# oneboard.net
KiCad netlist of a schematic drawn in EAGLE
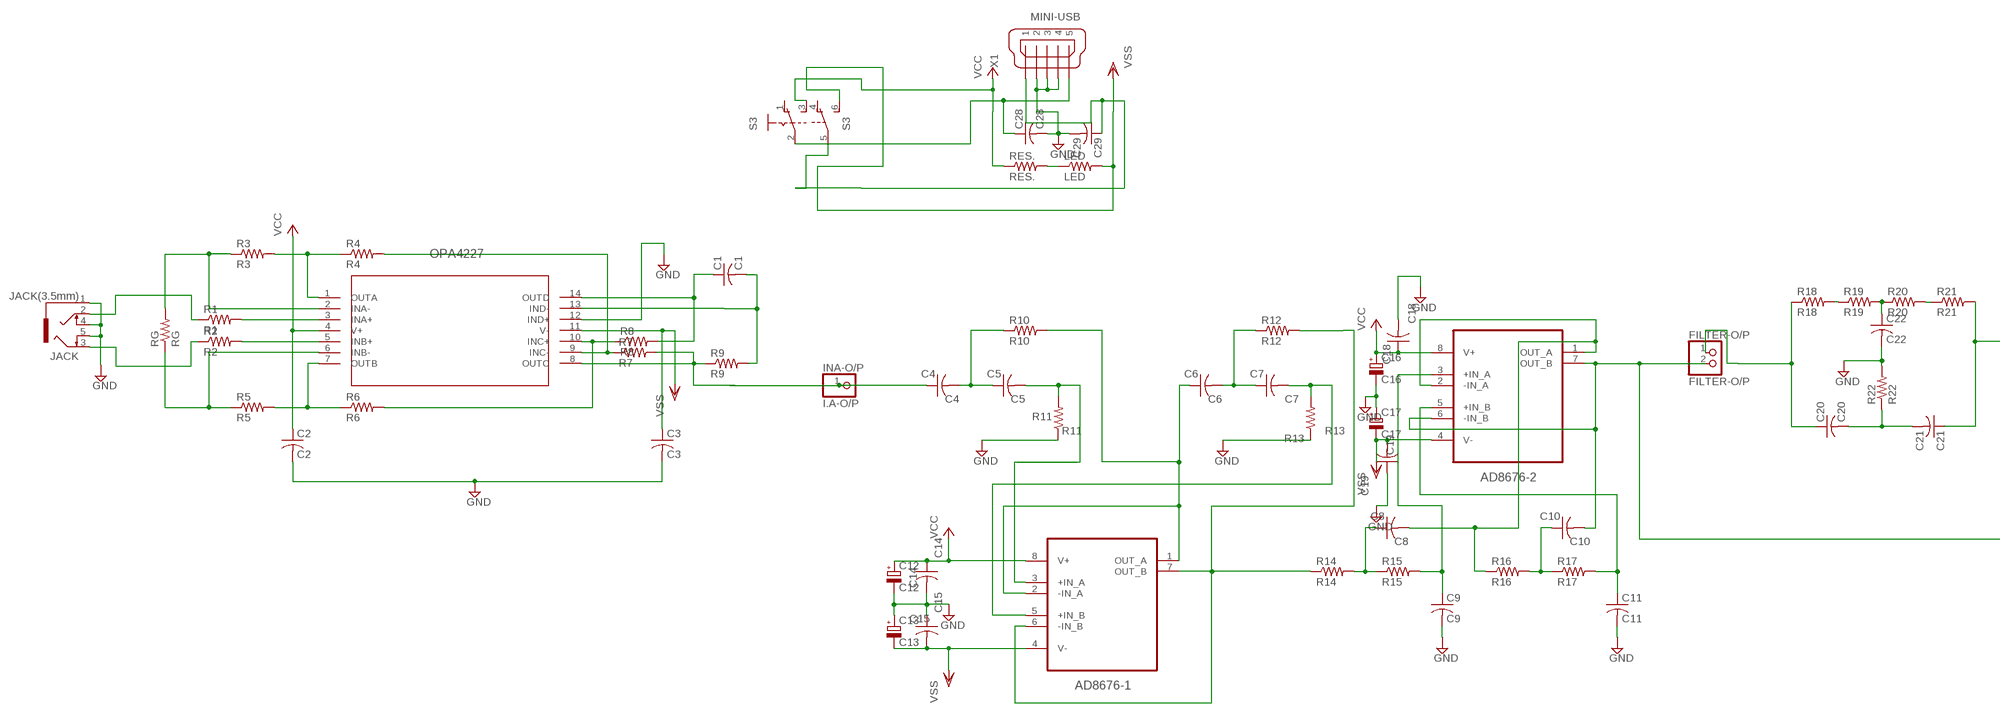
[diagram p0: schematic, sheet 1, part 1 of 2]
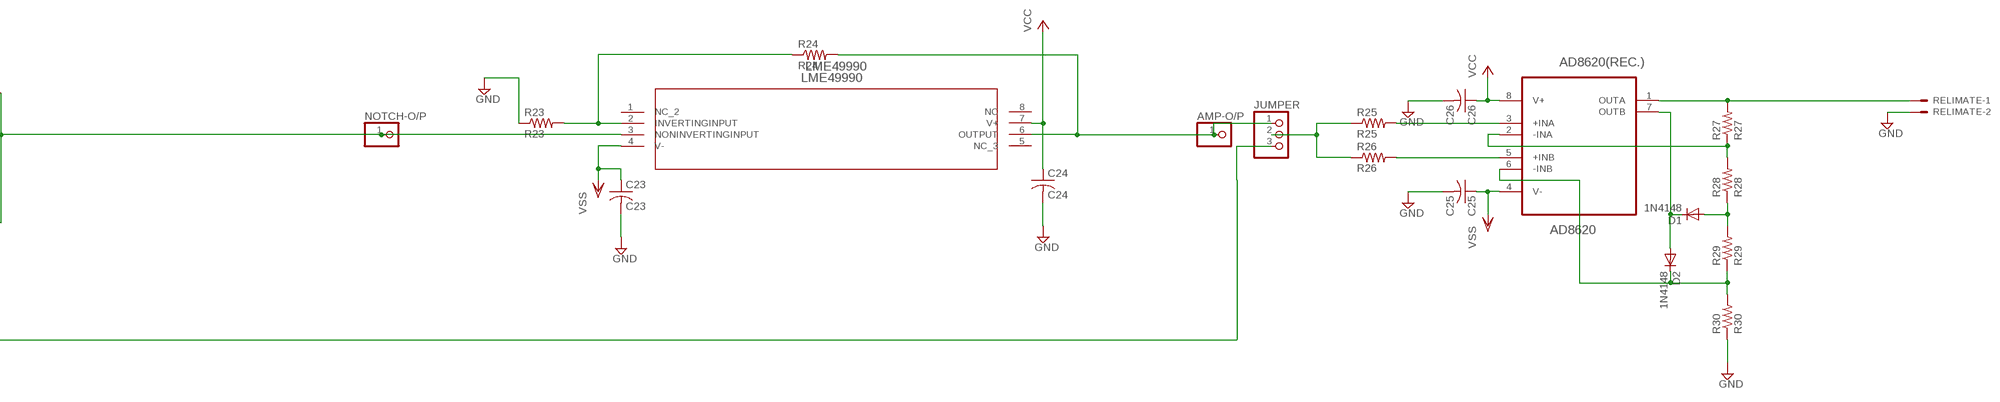
[diagram p1: schematic, sheet 1, part 2 of 2]

(export (version "E")
  (design (tool "Eeschema 10.0.6"))
  (components
    (comp (ref "AD8620(REC.)")
      (value "AD8620")
      (footprint "eagle-import:SOIC127P600X175-8N")
      (fields (field (name "MPN") "AD8620ARZ"))
      (libsource (lib "eagle-import") (part "AD8620ARZ"))
    )
    (comp (ref "AD8676-1")
      (value "AD8676-1")
      (footprint "eagle-import:SOIC127P600X175-8N")
      (fields (field (name "MPN") "AD8676ARZ"))
      (libsource (lib "eagle-import") (part "AD8676ARZ"))
    )
    (comp (ref "AD8676-2")
      (value "AD8676-2")
      (footprint "eagle-import:SOIC127P600X175-8N")
      (fields (field (name "MPN") "AD8676ARZ"))
      (libsource (lib "eagle-import") (part "AD8676ARZ"))
    )
    (comp (ref "AMP-O/P")
      (value "PINHD-1X1")
      (footprint "eagle-import:1X01")
      (libsource (lib "eagle-import") (part "PINHD-1X1"))
    )
    (comp (ref "C1")
      (value "C1")
      (footprint "eagle-import:C0603")
      (libsource (lib "eagle-import") (part "C-USC0603"))
    )
    (comp (ref "C2")
      (value "C2")
      (footprint "eagle-import:C0603")
      (libsource (lib "eagle-import") (part "C-USC0603"))
    )
    (comp (ref "C3")
      (value "C3")
      (footprint "eagle-import:C0603")
      (libsource (lib "eagle-import") (part "C-USC0603"))
    )
    (comp (ref "C4")
      (value "C4")
      (footprint "eagle-import:C0603")
      (libsource (lib "eagle-import") (part "C-USC0603"))
    )
    (comp (ref "C5")
      (value "C5")
      (footprint "eagle-import:C0603")
      (libsource (lib "eagle-import") (part "C-USC0603"))
    )
    (comp (ref "C6")
      (value "C6")
      (footprint "eagle-import:C0603")
      (libsource (lib "eagle-import") (part "C-USC0603"))
    )
    (comp (ref "C7")
      (value "C7")
      (footprint "eagle-import:C0603")
      (libsource (lib "eagle-import") (part "C-USC0603"))
    )
    (comp (ref "C8")
      (value "C8")
      (footprint "eagle-import:C0603")
      (libsource (lib "eagle-import") (part "C-USC0603"))
    )
    (comp (ref "C9")
      (value "C9")
      (footprint "eagle-import:C0603")
      (libsource (lib "eagle-import") (part "C-USC0603"))
    )
    (comp (ref "C10")
      (value "C10")
      (footprint "eagle-import:C0603")
      (libsource (lib "eagle-import") (part "C-USC0603"))
    )
    (comp (ref "C11")
      (value "C11")
      (footprint "eagle-import:C0603")
      (libsource (lib "eagle-import") (part "C-USC0603"))
    )
    (comp (ref "C12")
      (value "C12")
      (footprint "eagle-import:E2-5")
      (libsource (lib "eagle-import") (part "CPOL-EUE2-5"))
    )
    (comp (ref "C13")
      (value "C13")
      (footprint "eagle-import:E2-5")
      (libsource (lib "eagle-import") (part "CPOL-EUE2-5"))
    )
    (comp (ref "C14")
      (value "C14")
      (footprint "eagle-import:C0603")
      (libsource (lib "eagle-import") (part "C-USC0603"))
    )
    (comp (ref "C15")
      (value "C15")
      (footprint "eagle-import:C0603")
      (libsource (lib "eagle-import") (part "C-USC0603"))
    )
    (comp (ref "C16")
      (value "C16")
      (footprint "eagle-import:E2-5")
      (libsource (lib "eagle-import") (part "CPOL-EUE2-5"))
    )
    (comp (ref "C17")
      (value "C17")
      (footprint "eagle-import:E2-5")
      (libsource (lib "eagle-import") (part "CPOL-EUE2-5"))
    )
    (comp (ref "C18")
      (value "C18")
      (footprint "eagle-import:C0603")
      (libsource (lib "eagle-import") (part "C-USC0603"))
    )
    (comp (ref "C19")
      (value "C19")
      (footprint "eagle-import:C0603")
      (libsource (lib "eagle-import") (part "C-USC0603"))
    )
    (comp (ref "C20")
      (value "C20")
      (footprint "eagle-import:C0603")
      (libsource (lib "eagle-import") (part "C-USC0603"))
    )
    (comp (ref "C21")
      (value "C21")
      (footprint "eagle-import:C0603")
      (libsource (lib "eagle-import") (part "C-USC0603"))
    )
    (comp (ref "C22")
      (value "C22")
      (footprint "eagle-import:C0603")
      (libsource (lib "eagle-import") (part "C-USC0603"))
    )
    (comp (ref "C23")
      (value "C23")
      (footprint "eagle-import:C0603")
      (libsource (lib "eagle-import") (part "C-USC0603"))
    )
    (comp (ref "C24")
      (value "C24")
      (footprint "eagle-import:C0603")
      (libsource (lib "eagle-import") (part "C-USC0603"))
    )
    (comp (ref "C25")
      (value "C25")
      (footprint "eagle-import:C0603")
      (libsource (lib "eagle-import") (part "C-USC0603"))
    )
    (comp (ref "C26")
      (value "C26")
      (footprint "eagle-import:C0603")
      (libsource (lib "eagle-import") (part "C-USC0603"))
    )
    (comp (ref "C28")
      (value "C28")
      (footprint "eagle-import:C0603")
      (libsource (lib "eagle-import") (part "C-USC0603"))
    )
    (comp (ref "C29")
      (value "C29")
      (footprint "eagle-import:C0603")
      (libsource (lib "eagle-import") (part "C-USC0603"))
    )
    (comp (ref "D1")
      (value "1N4148")
      (footprint "eagle-import:DO35-10")
      (libsource (lib "eagle-import") (part "1N4148DO35-10"))
    )
    (comp (ref "D2")
      (value "1N4148")
      (footprint "eagle-import:DO35-10")
      (libsource (lib "eagle-import") (part "1N4148DO35-10"))
    )
    (comp (ref "FILTER-O/P")
      (value "FILTER-O/P")
      (footprint "eagle-import:1X02")
      (libsource (lib "eagle-import") (part "PINHD-1X2"))
    )
    (comp (ref "INA-O/P")
      (value "I.A-O/P")
      (footprint "eagle-import:1X01")
      (libsource (lib "eagle-import") (part "PINHD-1X1"))
    )
    (comp (ref "JACK")
      (value "JACK(3.5mm)")
      (footprint "eagle-import:1503_09")
      (libsource (lib "eagle-import") (part "1503_09"))
    )
    (comp (ref "JUMPER")
      (value "PINHD-1X3")
      (footprint "eagle-import:1X03")
      (libsource (lib "eagle-import") (part "PINHD-1X3"))
    )
    (comp (ref "LED")
      (value "LED")
      (footprint "eagle-import:R0805")
      (libsource (lib "eagle-import") (part "R-US_R0805"))
    )
    (comp (ref "LME49990")
      (value "LME49990")
      (footprint "eagle-import:M08A")
      (fields
        (field (name "MANUFACTURER") "Texas Instruments")
        (field (name "MANUFACTURER_PART_NUMBER") "lme49990_d_8")
      )
      (libsource (lib "eagle-import") (part "LME49990_D_8"))
    )
    (comp (ref "NOTCH-O/P")
      (value "PINHD-1X1")
      (footprint "eagle-import:1X01")
      (libsource (lib "eagle-import") (part "PINHD-1X1"))
    )
    (comp (ref "OPA4227")
      (value "OPA4277_D_14")
      (footprint "eagle-import:D14")
      (fields
        (field (name "GENERIC_PART_NUMBER") "OPA4277")
        (field (name "MANUFACTURER") "Texas Instruments")
        (field (name "MANUFACTURER_PART_NUMBER") "opa4277_d_14")
      )
      (libsource (lib "eagle-import") (part "OPA4277_D_14"))
    )
    (comp (ref "R1")
      (value "R1")
      (footprint "eagle-import:R0603")
      (libsource (lib "eagle-import") (part "resistor_R-US_R0603"))
    )
    (comp (ref "R2")
      (value "R2")
      (footprint "eagle-import:R0603")
      (libsource (lib "eagle-import") (part "resistor_R-US_R0603"))
    )
    (comp (ref "R3")
      (value "R3")
      (footprint "eagle-import:R0603")
      (libsource (lib "eagle-import") (part "resistor_R-US_R0603"))
    )
    (comp (ref "R4")
      (value "R4")
      (footprint "eagle-import:R0603")
      (libsource (lib "eagle-import") (part "resistor_R-US_R0603"))
    )
    (comp (ref "R5")
      (value "R5")
      (footprint "eagle-import:R0603")
      (libsource (lib "eagle-import") (part "resistor_R-US_R0603"))
    )
    (comp (ref "R6")
      (value "R6")
      (footprint "eagle-import:R0603")
      (libsource (lib "eagle-import") (part "resistor_R-US_R0603"))
    )
    (comp (ref "R7")
      (value "R7")
      (footprint "eagle-import:R0603")
      (libsource (lib "eagle-import") (part "resistor_R-US_R0603"))
    )
    (comp (ref "R8")
      (value "R8")
      (footprint "eagle-import:R0603")
      (libsource (lib "eagle-import") (part "resistor_R-US_R0603"))
    )
    (comp (ref "R9")
      (value "R9")
      (footprint "eagle-import:R0603")
      (libsource (lib "eagle-import") (part "resistor_R-US_R0603"))
    )
    (comp (ref "R10")
      (value "R10")
      (footprint "eagle-import:R0603")
      (libsource (lib "eagle-import") (part "R-US_R0603"))
    )
    (comp (ref "R11")
      (value "R11")
      (footprint "eagle-import:R0603")
      (libsource (lib "eagle-import") (part "R-US_R0603"))
    )
    (comp (ref "R12")
      (value "R12")
      (footprint "eagle-import:R0603")
      (libsource (lib "eagle-import") (part "R-US_R0603"))
    )
    (comp (ref "R13")
      (value "R13")
      (footprint "eagle-import:R0603")
      (libsource (lib "eagle-import") (part "R-US_R0603"))
    )
    (comp (ref "R14")
      (value "R14")
      (footprint "eagle-import:R0603")
      (libsource (lib "eagle-import") (part "R-US_R0603"))
    )
    (comp (ref "R15")
      (value "R15")
      (footprint "eagle-import:R0603")
      (libsource (lib "eagle-import") (part "R-US_R0603"))
    )
    (comp (ref "R16")
      (value "R16")
      (footprint "eagle-import:R0603")
      (libsource (lib "eagle-import") (part "R-US_R0603"))
    )
    (comp (ref "R17")
      (value "R17")
      (footprint "eagle-import:R0603")
      (libsource (lib "eagle-import") (part "R-US_R0603"))
    )
    (comp (ref "R18")
      (value "R18")
      (footprint "eagle-import:R0603")
      (libsource (lib "eagle-import") (part "R-US_R0603"))
    )
    (comp (ref "R19")
      (value "R19")
      (footprint "eagle-import:R0603")
      (libsource (lib "eagle-import") (part "R-US_R0603"))
    )
    (comp (ref "R20")
      (value "R20")
      (footprint "eagle-import:R0603")
      (libsource (lib "eagle-import") (part "R-US_R0603"))
    )
    (comp (ref "R21")
      (value "R21")
      (footprint "eagle-import:R0603")
      (libsource (lib "eagle-import") (part "R-US_R0603"))
    )
    (comp (ref "R22")
      (value "R22")
      (footprint "eagle-import:R0603")
      (libsource (lib "eagle-import") (part "R-US_R0603"))
    )
    (comp (ref "R23")
      (value "R23")
      (footprint "eagle-import:R0603")
      (libsource (lib "eagle-import") (part "R-US_R0603"))
    )
    (comp (ref "R24")
      (value "R24")
      (footprint "eagle-import:R0603")
      (libsource (lib "eagle-import") (part "R-US_R0603"))
    )
    (comp (ref "R25")
      (value "R25")
      (footprint "eagle-import:R0603")
      (libsource (lib "eagle-import") (part "R-US_R0603"))
    )
    (comp (ref "R26")
      (value "R26")
      (footprint "eagle-import:R0603")
      (libsource (lib "eagle-import") (part "R-US_R0603"))
    )
    (comp (ref "R27")
      (value "R27")
      (footprint "eagle-import:R0603")
      (libsource (lib "eagle-import") (part "R-US_R0603"))
    )
    (comp (ref "R28")
      (value "R28")
      (footprint "eagle-import:R0603")
      (libsource (lib "eagle-import") (part "R-US_R0603"))
    )
    (comp (ref "R29")
      (value "R29")
      (footprint "eagle-import:R0603")
      (libsource (lib "eagle-import") (part "R-US_R0603"))
    )
    (comp (ref "R30")
      (value "R30")
      (footprint "eagle-import:R0603")
      (libsource (lib "eagle-import") (part "R-US_R0603"))
    )
    (comp (ref "RELIMATE")
      (value "22-23-2021")
      (footprint "eagle-import:22-23-2021")
      (fields (field (name "MF") "MOLEX"))
      (libsource (lib "eagle-import") (part "22-23-2021"))
    )
    (comp (ref "RES.")
      (value "RES.")
      (footprint "eagle-import:R0603")
      (libsource (lib "eagle-import") (part "R-US_R0603"))
    )
    (comp (ref "RG")
      (value "RG")
      (footprint "eagle-import:R0603")
      (libsource (lib "eagle-import") (part "resistor_R-US_R0603"))
    )
    (comp (ref "S3")
      (value "A68-A31")
      (footprint "eagle-import:A68-A31")
      (libsource (lib "eagle-import") (part "A68-A31"))
    )
    (comp (ref "X1")
      (value "MINI-USB")
      (footprint "eagle-import:UX60-MB-5S8")
      (libsource (lib "eagle-import") (part "MINI-USB-UX60-MB-5S8"))
    )
  )
  (nets
    (net (code "1") (name "GND") (class "Default")
      (node (ref "C11") (pin "2") (pinfunction "2_2") (pintype "passive"))
      (node (ref "C12") (pin "-") (pinfunction "-_-") (pintype "passive"))
      (node (ref "C13") (pin "+") (pinfunction "+_+") (pintype "passive"))
      (node (ref "C14") (pin "2") (pinfunction "2_2") (pintype "passive"))
      (node (ref "C15") (pin "1") (pinfunction "1_1") (pintype "passive"))
      (node (ref "C16") (pin "-") (pinfunction "-_-") (pintype "passive"))
      (node (ref "C17") (pin "+") (pinfunction "+_+") (pintype "passive"))
      (node (ref "C18") (pin "2") (pinfunction "2_2") (pintype "passive"))
      (node (ref "C19") (pin "1") (pinfunction "1_1") (pintype "passive"))
      (node (ref "C2") (pin "2") (pinfunction "2_2") (pintype "passive"))
      (node (ref "C22") (pin "2") (pinfunction "2_2") (pintype "passive"))
      (node (ref "C23") (pin "2") (pinfunction "2_2") (pintype "passive"))
      (node (ref "C24") (pin "2") (pinfunction "2_2") (pintype "passive"))
      (node (ref "C25") (pin "2") (pinfunction "2_2") (pintype "passive"))
      (node (ref "C26") (pin "2") (pinfunction "2_2") (pintype "passive"))
      (node (ref "C28") (pin "2") (pinfunction "2_2") (pintype "passive"))
      (node (ref "C29") (pin "2") (pinfunction "2_2") (pintype "passive"))
      (node (ref "C3") (pin "2") (pinfunction "2_2") (pintype "passive"))
      (node (ref "C9") (pin "2") (pinfunction "2_2") (pintype "passive"))
      (node (ref "JACK") (pin "1") (pinfunction "1_1") (pintype "passive"))
      (node (ref "JACK") (pin "4") (pinfunction "4_4") (pintype "passive"))
      (node (ref "JACK") (pin "5") (pinfunction "5_5") (pintype "passive"))
      (node (ref "OPA4227") (pin "12") (pinfunction "IND+_12") (pintype "input"))
      (node (ref "R11") (pin "1") (pinfunction "1_1") (pintype "passive"))
      (node (ref "R13") (pin "1") (pinfunction "1_1") (pintype "passive"))
      (node (ref "R22") (pin "2") (pinfunction "2_2") (pintype "passive"))
      (node (ref "R23") (pin "1") (pinfunction "1_1") (pintype "passive"))
      (node (ref "R30") (pin "1") (pinfunction "1_1") (pintype "passive"))
      (node (ref "RELIMATE") (pin "2") (pinfunction "S_2") (pintype "passive"))
      (node (ref "X1") (pin "2") (pinfunction "2_2") (pintype "input"))
      (node (ref "X1") (pin "3") (pinfunction "3_3") (pintype "input"))
      (node (ref "X1") (pin "4") (pinfunction "4_4") (pintype "input"))
    )
    (net (code "2") (name "Net-(AD8620(REC.)-+INA)") (class "Default")
      (node (ref "AD8620(REC.)") (pin "3") (pinfunction "+INA_3") (pintype "input"))
      (node (ref "R25") (pin "2") (pinfunction "2_2") (pintype "passive"))
    )
    (net (code "3") (name "Net-(AD8620(REC.)-+INB)") (class "Default")
      (node (ref "AD8620(REC.)") (pin "5") (pinfunction "+INB_5") (pintype "input"))
      (node (ref "R26") (pin "2") (pinfunction "2_2") (pintype "passive"))
    )
    (net (code "4") (name "Net-(AD8620(REC.)--INA)") (class "Default")
      (node (ref "AD8620(REC.)") (pin "2") (pinfunction "-INA_2") (pintype "input"))
      (node (ref "R27") (pin "1") (pinfunction "1_1") (pintype "passive"))
      (node (ref "R28") (pin "2") (pinfunction "2_2") (pintype "passive"))
    )
    (net (code "5") (name "Net-(AD8620(REC.)--INB)") (class "Default")
      (node (ref "AD8620(REC.)") (pin "6") (pinfunction "-INB_6") (pintype "input"))
      (node (ref "D2") (pin "C") (pinfunction "C_C") (pintype "passive"))
      (node (ref "R29") (pin "1") (pinfunction "1_1") (pintype "passive"))
      (node (ref "R30") (pin "2") (pinfunction "2_2") (pintype "passive"))
    )
    (net (code "6") (name "Net-(AD8620(REC.)-OUTA)") (class "Default")
      (node (ref "AD8620(REC.)") (pin "1") (pinfunction "OUTA_1") (pintype "output"))
      (node (ref "R27") (pin "2") (pinfunction "2_2") (pintype "passive"))
      (node (ref "RELIMATE") (pin "1") (pinfunction "S_1") (pintype "passive"))
    )
    (net (code "7") (name "Net-(AD8620(REC.)-OUTB)") (class "Default")
      (node (ref "AD8620(REC.)") (pin "7") (pinfunction "OUTB_7") (pintype "output"))
      (node (ref "D1") (pin "C") (pinfunction "C_C") (pintype "passive"))
      (node (ref "D2") (pin "A") (pinfunction "A_A") (pintype "passive"))
    )
    (net (code "8") (name "Net-(AD8676-1-+IN_A)") (class "Default")
      (node (ref "AD8676-1") (pin "3") (pinfunction "+IN_A_3") (pintype "input"))
      (node (ref "C5") (pin "2") (pinfunction "2_2") (pintype "passive"))
      (node (ref "R11") (pin "2") (pinfunction "2_2") (pintype "passive"))
    )
    (net (code "9") (name "Net-(AD8676-1-+IN_B)") (class "Default")
      (node (ref "AD8676-1") (pin "5") (pinfunction "+IN_B_5") (pintype "input"))
      (node (ref "C7") (pin "2") (pinfunction "2_2") (pintype "passive"))
      (node (ref "R13") (pin "2") (pinfunction "2_2") (pintype "passive"))
    )
    (net (code "10") (name "Net-(AD8676-1--IN_A)") (class "Default")
      (node (ref "AD8676-1") (pin "1") (pinfunction "OUT_A_1") (pintype "output"))
      (node (ref "AD8676-1") (pin "2") (pinfunction "-IN_A_2") (pintype "input"))
      (node (ref "C6") (pin "1") (pinfunction "1_1") (pintype "passive"))
      (node (ref "R10") (pin "2") (pinfunction "2_2") (pintype "passive"))
    )
    (net (code "11") (name "Net-(AD8676-1--IN_B)") (class "Default")
      (node (ref "AD8676-1") (pin "6") (pinfunction "-IN_B_6") (pintype "input"))
      (node (ref "AD8676-1") (pin "7") (pinfunction "OUT_B_7") (pintype "output"))
      (node (ref "R12") (pin "2") (pinfunction "2_2") (pintype "passive"))
      (node (ref "R14") (pin "1") (pinfunction "1_1") (pintype "passive"))
    )
    (net (code "12") (name "Net-(AD8676-2-+IN_A)") (class "Default")
      (node (ref "AD8676-2") (pin "3") (pinfunction "+IN_A_3") (pintype "input"))
      (node (ref "C9") (pin "1") (pinfunction "1_1") (pintype "passive"))
      (node (ref "R15") (pin "2") (pinfunction "2_2") (pintype "passive"))
    )
    (net (code "13") (name "Net-(AD8676-2-+IN_B)") (class "Default")
      (node (ref "AD8676-2") (pin "5") (pinfunction "+IN_B_5") (pintype "input"))
      (node (ref "C11") (pin "1") (pinfunction "1_1") (pintype "passive"))
      (node (ref "R17") (pin "2") (pinfunction "2_2") (pintype "passive"))
    )
    (net (code "14") (name "Net-(AD8676-2--IN_A)") (class "Default")
      (node (ref "AD8676-2") (pin "1") (pinfunction "OUT_A_1") (pintype "output"))
      (node (ref "AD8676-2") (pin "2") (pinfunction "-IN_A_2") (pintype "input"))
      (node (ref "C8") (pin "2") (pinfunction "2_2") (pintype "passive"))
      (node (ref "R16") (pin "1") (pinfunction "1_1") (pintype "passive"))
    )
    (net (code "15") (name "Net-(AD8676-2--IN_B)") (class "Default")
      (node (ref "AD8676-2") (pin "6") (pinfunction "-IN_B_6") (pintype "input"))
      (node (ref "AD8676-2") (pin "7") (pinfunction "OUT_B_7") (pintype "output"))
      (node (ref "C10") (pin "2") (pinfunction "2_2") (pintype "passive"))
      (node (ref "FILTER-O/P") (pin "2") (pinfunction "2_2") (pintype "passive"))
      (node (ref "JUMPER") (pin "3") (pinfunction "3_3") (pintype "passive"))
    )
    (net (code "16") (name "Net-(C4-Pad2)") (class "Default")
      (node (ref "C4") (pin "2") (pinfunction "2_2") (pintype "passive"))
      (node (ref "C5") (pin "1") (pinfunction "1_1") (pintype "passive"))
      (node (ref "R10") (pin "1") (pinfunction "1_1") (pintype "passive"))
    )
    (net (code "17") (name "Net-(C6-Pad2)") (class "Default")
      (node (ref "C6") (pin "2") (pinfunction "2_2") (pintype "passive"))
      (node (ref "C7") (pin "1") (pinfunction "1_1") (pintype "passive"))
      (node (ref "R12") (pin "1") (pinfunction "1_1") (pintype "passive"))
    )
    (net (code "18") (name "Net-(C8-Pad1)") (class "Default")
      (node (ref "C8") (pin "1") (pinfunction "1_1") (pintype "passive"))
      (node (ref "R14") (pin "2") (pinfunction "2_2") (pintype "passive"))
      (node (ref "R15") (pin "1") (pinfunction "1_1") (pintype "passive"))
    )
    (net (code "19") (name "Net-(C10-Pad1)") (class "Default")
      (node (ref "C10") (pin "1") (pinfunction "1_1") (pintype "passive"))
      (node (ref "R16") (pin "2") (pinfunction "2_2") (pintype "passive"))
      (node (ref "R17") (pin "1") (pinfunction "1_1") (pintype "passive"))
    )
    (net (code "20") (name "Net-(C20-Pad1)") (class "Default")
      (node (ref "C20") (pin "1") (pinfunction "1_1") (pintype "passive"))
      (node (ref "FILTER-O/P") (pin "1") (pinfunction "1_1") (pintype "passive"))
      (node (ref "R18") (pin "1") (pinfunction "1_1") (pintype "passive"))
    )
    (net (code "21") (name "Net-(C20-Pad2)") (class "Default")
      (node (ref "C20") (pin "2") (pinfunction "2_2") (pintype "passive"))
      (node (ref "C21") (pin "2") (pinfunction "2_2") (pintype "passive"))
      (node (ref "R22") (pin "1") (pinfunction "1_1") (pintype "passive"))
    )
    (net (code "22") (name "Net-(C22-Pad1)") (class "Default")
      (node (ref "C22") (pin "1") (pinfunction "1_1") (pintype "passive"))
      (node (ref "R19") (pin "2") (pinfunction "2_2") (pintype "passive"))
      (node (ref "R20") (pin "1") (pinfunction "1_1") (pintype "passive"))
    )
    (net (code "23") (name "Net-(D1-PadA)") (class "Default")
      (node (ref "D1") (pin "A") (pinfunction "A_A") (pintype "passive"))
      (node (ref "R28") (pin "1") (pinfunction "1_1") (pintype "passive"))
      (node (ref "R29") (pin "2") (pinfunction "2_2") (pintype "passive"))
    )
    (net (code "24") (name "Net-(JACK-Pad2)") (class "Default")
      (node (ref "JACK") (pin "2") (pinfunction "2_2") (pintype "passive"))
      (node (ref "R1") (pin "1") (pinfunction "1_1") (pintype "passive"))
    )
    (net (code "25") (name "Net-(JACK-Pad3)") (class "Default")
      (node (ref "JACK") (pin "3") (pinfunction "3_3") (pintype "passive"))
      (node (ref "R2") (pin "1") (pinfunction "1_1") (pintype "passive"))
    )
    (net (code "26") (name "Net-(JUMPER-Pad2)") (class "Default")
      (node (ref "JUMPER") (pin "2") (pinfunction "2_2") (pintype "passive"))
      (node (ref "R25") (pin "1") (pinfunction "1_1") (pintype "passive"))
      (node (ref "R26") (pin "1") (pinfunction "1_1") (pintype "passive"))
    )
    (net (code "27") (name "Net-(LED-Pad1)") (class "Default")
      (node (ref "LED") (pin "1") (pinfunction "1_1") (pintype "passive"))
      (node (ref "RES.") (pin "2") (pinfunction "2_2") (pintype "passive"))
    )
    (net (code "28") (name "Net-(LME49990-INVERTINGINPUT)") (class "Default")
      (node (ref "LME49990") (pin "2") (pinfunction "INVERTINGINPUT_2") (pintype "input"))
      (node (ref "R23") (pin "2") (pinfunction "2_2") (pintype "passive"))
      (node (ref "R24") (pin "1") (pinfunction "1_1") (pintype "passive"))
    )
    (net (code "29") (name "Net-(LME49990-NONINVERTINGINPUT)") (class "Default")
      (node (ref "C21") (pin "1") (pinfunction "1_1") (pintype "passive"))
      (node (ref "LME49990") (pin "3") (pinfunction "NONINVERTINGINPUT_3") (pintype "input"))
      (node (ref "NOTCH-O/P") (pin "1") (pinfunction "1_1") (pintype "passive"))
      (node (ref "R21") (pin "2") (pinfunction "2_2") (pintype "passive"))
    )
    (net (code "30") (name "Net-(LME49990-OUTPUT)") (class "Default")
      (node (ref "AMP-O/P") (pin "1") (pinfunction "1_1") (pintype "passive"))
      (node (ref "JUMPER") (pin "1") (pinfunction "1_1") (pintype "passive"))
      (node (ref "LME49990") (pin "6") (pinfunction "OUTPUT_6") (pintype "output"))
      (node (ref "R24") (pin "2") (pinfunction "2_2") (pintype "passive"))
    )
    (net (code "31") (name "Net-(OPA4227-INA+)") (class "Default")
      (node (ref "OPA4227") (pin "3") (pinfunction "INA+_3") (pintype "input"))
      (node (ref "R1") (pin "2") (pinfunction "2_2") (pintype "passive"))
    )
    (net (code "32") (name "Net-(OPA4227-INA-)") (class "Default")
      (node (ref "OPA4227") (pin "2") (pinfunction "INA-_2") (pintype "input"))
      (node (ref "R3") (pin "1") (pinfunction "1_1") (pintype "passive"))
      (node (ref "RG") (pin "2") (pinfunction "2_2") (pintype "passive"))
    )
    (net (code "33") (name "Net-(OPA4227-INB+)") (class "Default")
      (node (ref "OPA4227") (pin "5") (pinfunction "INB+_5") (pintype "input"))
      (node (ref "R2") (pin "2") (pinfunction "2_2") (pintype "passive"))
    )
    (net (code "34") (name "Net-(OPA4227-INB-)") (class "Default")
      (node (ref "OPA4227") (pin "6") (pinfunction "INB-_6") (pintype "input"))
      (node (ref "R5") (pin "1") (pinfunction "1_1") (pintype "passive"))
      (node (ref "RG") (pin "1") (pinfunction "1_1") (pintype "passive"))
    )
    (net (code "35") (name "Net-(OPA4227-INC+)") (class "Default")
      (node (ref "OPA4227") (pin "10") (pinfunction "INC+_10") (pintype "input"))
      (node (ref "R6") (pin "2") (pinfunction "2_2") (pintype "passive"))
      (node (ref "R8") (pin "1") (pinfunction "1_1") (pintype "passive"))
    )
    (net (code "36") (name "Net-(OPA4227-INC-)") (class "Default")
      (node (ref "OPA4227") (pin "9") (pinfunction "INC-_9") (pintype "input"))
      (node (ref "R4") (pin "2") (pinfunction "2_2") (pintype "passive"))
      (node (ref "R7") (pin "1") (pinfunction "1_1") (pintype "passive"))
    )
    (net (code "37") (name "Net-(OPA4227-IND-)") (class "Default")
      (node (ref "C1") (pin "2") (pinfunction "2_2") (pintype "passive"))
      (node (ref "OPA4227") (pin "13") (pinfunction "IND-_13") (pintype "input"))
      (node (ref "R9") (pin "2") (pinfunction "2_2") (pintype "passive"))
    )
    (net (code "38") (name "Net-(OPA4227-OUTA)") (class "Default")
      (node (ref "OPA4227") (pin "1") (pinfunction "OUTA_1") (pintype "output"))
      (node (ref "R3") (pin "2") (pinfunction "2_2") (pintype "passive"))
      (node (ref "R4") (pin "1") (pinfunction "1_1") (pintype "passive"))
    )
    (net (code "39") (name "Net-(OPA4227-OUTB)") (class "Default")
      (node (ref "OPA4227") (pin "7") (pinfunction "OUTB_7") (pintype "output"))
      (node (ref "R5") (pin "2") (pinfunction "2_2") (pintype "passive"))
      (node (ref "R6") (pin "1") (pinfunction "1_1") (pintype "passive"))
    )
    (net (code "40") (name "Net-(OPA4227-OUTC)") (class "Default")
      (node (ref "C4") (pin "1") (pinfunction "1_1") (pintype "passive"))
      (node (ref "INA-O/P") (pin "1") (pinfunction "1_1") (pintype "passive"))
      (node (ref "OPA4227") (pin "8") (pinfunction "OUTC_8") (pintype "output"))
      (node (ref "R7") (pin "2") (pinfunction "2_2") (pintype "passive"))
      (node (ref "R9") (pin "1") (pinfunction "1_1") (pintype "passive"))
    )
    (net (code "41") (name "Net-(OPA4227-OUTD)") (class "Default")
      (node (ref "C1") (pin "1") (pinfunction "1_1") (pintype "passive"))
      (node (ref "OPA4227") (pin "14") (pinfunction "OUTD_14") (pintype "output"))
      (node (ref "R8") (pin "2") (pinfunction "2_2") (pintype "passive"))
    )
    (net (code "42") (name "Net-(R18-Pad2)") (class "Default")
      (node (ref "R18") (pin "2") (pinfunction "2_2") (pintype "passive"))
      (node (ref "R19") (pin "1") (pinfunction "1_1") (pintype "passive"))
    )
    (net (code "43") (name "Net-(R20-Pad2)") (class "Default")
      (node (ref "R20") (pin "2") (pinfunction "2_2") (pintype "passive"))
      (node (ref "R21") (pin "1") (pinfunction "1_1") (pintype "passive"))
    )
    (net (code "44") (name "Net-(S3A-P)") (class "Default")
      (node (ref "C28") (pin "1") (pinfunction "1_1") (pintype "passive"))
      (node (ref "S3") (pin "2") (pinfunction "P_2") (pintype "passive"))
      (node (ref "X1") (pin "5") (pinfunction "5_5") (pintype "input"))
    )
    (net (code "45") (name "Net-(S3B-P)") (class "Default")
      (node (ref "C29") (pin "1") (pinfunction "1_1") (pintype "passive"))
      (node (ref "S3") (pin "5") (pinfunction "P_5") (pintype "passive"))
      (node (ref "X1") (pin "1") (pinfunction "1_1") (pintype "input"))
    )
    (net (code "46") (name "VCC") (class "Default")
      (node (ref "AD8620(REC.)") (pin "8") (pinfunction "V+_8") (pintype "power_in"))
      (node (ref "AD8676-1") (pin "8") (pinfunction "V+_8") (pintype "power_in"))
      (node (ref "AD8676-2") (pin "8") (pinfunction "V+_8") (pintype "power_in"))
      (node (ref "C12") (pin "+") (pinfunction "+_+") (pintype "passive"))
      (node (ref "C14") (pin "1") (pinfunction "1_1") (pintype "passive"))
      (node (ref "C16") (pin "+") (pinfunction "+_+") (pintype "passive"))
      (node (ref "C18") (pin "1") (pinfunction "1_1") (pintype "passive"))
      (node (ref "C2") (pin "1") (pinfunction "1_1") (pintype "passive"))
      (node (ref "C24") (pin "1") (pinfunction "1_1") (pintype "passive"))
      (node (ref "C26") (pin "1") (pinfunction "1_1") (pintype "passive"))
      (node (ref "LME49990") (pin "7") (pinfunction "V+_7") (pintype "power_in"))
      (node (ref "OPA4227") (pin "4") (pinfunction "V+_4") (pintype "power_in"))
      (node (ref "RES.") (pin "1") (pinfunction "1_1") (pintype "passive"))
      (node (ref "S3") (pin "3") (pinfunction "S_3") (pintype "passive"))
    )
    (net (code "47") (name "VSS") (class "Default")
      (node (ref "AD8620(REC.)") (pin "4") (pinfunction "V-_4") (pintype "power_in"))
      (node (ref "AD8676-1") (pin "4") (pinfunction "V-_4") (pintype "power_in"))
      (node (ref "AD8676-2") (pin "4") (pinfunction "V-_4") (pintype "power_in"))
      (node (ref "C13") (pin "-") (pinfunction "-_-") (pintype "passive"))
      (node (ref "C15") (pin "2") (pinfunction "2_2") (pintype "passive"))
      (node (ref "C17") (pin "-") (pinfunction "-_-") (pintype "passive"))
      (node (ref "C19") (pin "2") (pinfunction "2_2") (pintype "passive"))
      (node (ref "C23") (pin "1") (pinfunction "1_1") (pintype "passive"))
      (node (ref "C25") (pin "1") (pinfunction "1_1") (pintype "passive"))
      (node (ref "C3") (pin "1") (pinfunction "1_1") (pintype "passive"))
      (node (ref "LED") (pin "2") (pinfunction "2_2") (pintype "passive"))
      (node (ref "LME49990") (pin "4") (pinfunction "V-_4") (pintype "power_in"))
      (node (ref "OPA4227") (pin "11") (pinfunction "V-_11") (pintype "power_in"))
      (node (ref "S3") (pin "6") (pinfunction "S_6") (pintype "passive"))
    )
    (net (code "48") (name "unconnected-(LME49990-NC-Pad8)") (class "Default")
      (node (ref "LME49990") (pin "8") (pinfunction "NC_8") (pintype "no_connect"))
    )
    (net (code "49") (name "unconnected-(LME49990-NC_2-Pad1)") (class "Default")
      (node (ref "LME49990") (pin "1") (pinfunction "NC_2_1") (pintype "no_connect"))
    )
    (net (code "50") (name "unconnected-(LME49990-NC_3-Pad5)") (class "Default")
      (node (ref "LME49990") (pin "5") (pinfunction "NC_3_5") (pintype "no_connect"))
    )
    (net (code "51") (name "unconnected-(S3A-O-Pad1)") (class "Default")
      (node (ref "S3") (pin "1") (pinfunction "O_1") (pintype "passive"))
    )
    (net (code "52") (name "unconnected-(S3B-O-Pad4)") (class "Default")
      (node (ref "S3") (pin "4") (pinfunction "O_4") (pintype "passive"))
    )
  )
)
